# USB-DDC.net
KiCad netlist of a schematic drawn in EAGLE
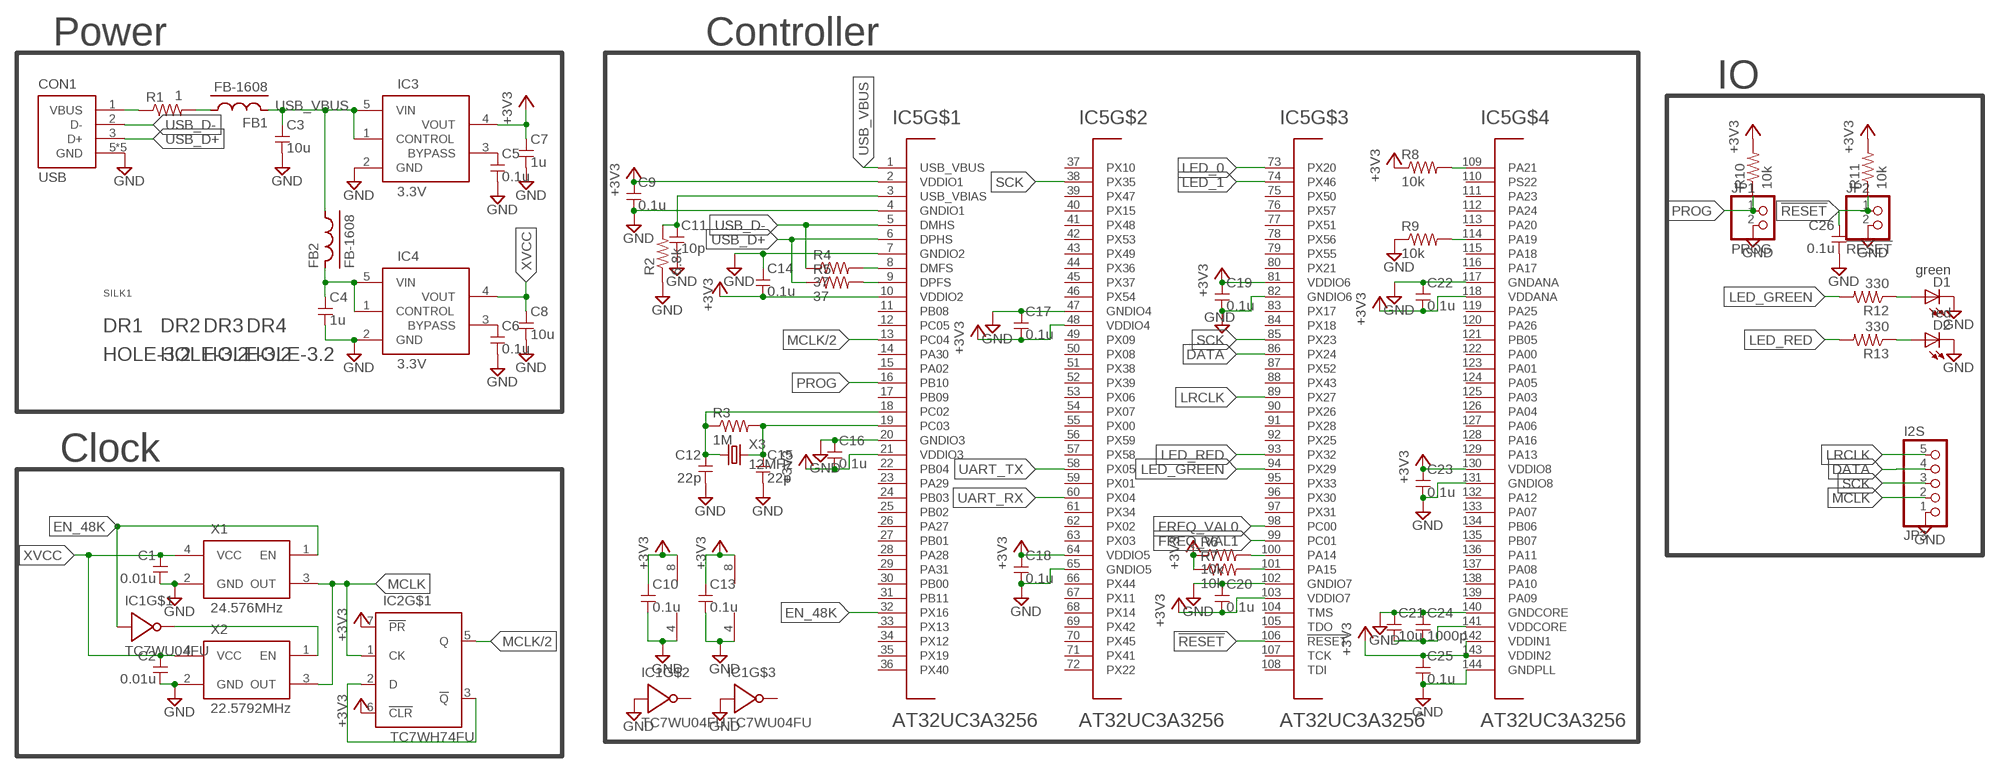
[diagram p0: schematic, sheet 1]

(export (version "E")
  (design (tool "Eeschema 10.0.6"))
  (components
    (comp (ref "C1")
      (value "0.01u")
      (footprint "eagle-import:1608")
      (libsource (lib "eagle-import") (part "C-1608"))
    )
    (comp (ref "C2")
      (value "0.01u")
      (footprint "eagle-import:1608")
      (libsource (lib "eagle-import") (part "C-1608"))
    )
    (comp (ref "C3")
      (value "10u")
      (footprint "eagle-import:2012")
      (libsource (lib "eagle-import") (part "C-2012"))
    )
    (comp (ref "C4")
      (value "1u")
      (footprint "eagle-import:1608")
      (libsource (lib "eagle-import") (part "C-1608"))
    )
    (comp (ref "C5")
      (value "0.1u")
      (footprint "eagle-import:1608")
      (libsource (lib "eagle-import") (part "C-1608"))
    )
    (comp (ref "C6")
      (value "0.1u")
      (footprint "eagle-import:1608")
      (libsource (lib "eagle-import") (part "C-1608"))
    )
    (comp (ref "C7")
      (value "1u")
      (footprint "eagle-import:2012")
      (libsource (lib "eagle-import") (part "C-2012"))
    )
    (comp (ref "C8")
      (value "10u")
      (footprint "eagle-import:2012")
      (libsource (lib "eagle-import") (part "C-2012"))
    )
    (comp (ref "C9")
      (value "0.1u")
      (footprint "eagle-import:1608")
      (libsource (lib "eagle-import") (part "C-1608"))
    )
    (comp (ref "C10")
      (value "0.1u")
      (footprint "eagle-import:1608")
      (libsource (lib "eagle-import") (part "C-1608"))
    )
    (comp (ref "C11")
      (value "10p")
      (footprint "eagle-import:1608")
      (libsource (lib "eagle-import") (part "C-1608"))
    )
    (comp (ref "C12")
      (value "22p")
      (footprint "eagle-import:1608")
      (libsource (lib "eagle-import") (part "C-1608"))
    )
    (comp (ref "C13")
      (value "0.1u")
      (footprint "eagle-import:1608")
      (libsource (lib "eagle-import") (part "C-1608"))
    )
    (comp (ref "C14")
      (value "0.1u")
      (footprint "eagle-import:1608")
      (libsource (lib "eagle-import") (part "C-1608"))
    )
    (comp (ref "C15")
      (value "22p")
      (footprint "eagle-import:1608")
      (libsource (lib "eagle-import") (part "C-1608"))
    )
    (comp (ref "C16")
      (value "0.1u")
      (footprint "eagle-import:1608")
      (libsource (lib "eagle-import") (part "C-1608"))
    )
    (comp (ref "C17")
      (value "0.1u")
      (footprint "eagle-import:1608")
      (libsource (lib "eagle-import") (part "C-1608"))
    )
    (comp (ref "C18")
      (value "0.1u")
      (footprint "eagle-import:1608")
      (libsource (lib "eagle-import") (part "C-1608"))
    )
    (comp (ref "C19")
      (value "0.1u")
      (footprint "eagle-import:1608")
      (libsource (lib "eagle-import") (part "C-1608"))
    )
    (comp (ref "C20")
      (value "0.1u")
      (footprint "eagle-import:1608")
      (libsource (lib "eagle-import") (part "C-1608"))
    )
    (comp (ref "C21")
      (value "10u")
      (footprint "eagle-import:2012")
      (libsource (lib "eagle-import") (part "C-2012"))
    )
    (comp (ref "C22")
      (value "0.1u")
      (footprint "eagle-import:1608")
      (libsource (lib "eagle-import") (part "C-1608"))
    )
    (comp (ref "C23")
      (value "0.1u")
      (footprint "eagle-import:1608")
      (libsource (lib "eagle-import") (part "C-1608"))
    )
    (comp (ref "C24")
      (value "1000p")
      (footprint "eagle-import:1608")
      (libsource (lib "eagle-import") (part "C-1608"))
    )
    (comp (ref "C25")
      (value "0.1u")
      (footprint "eagle-import:1608")
      (libsource (lib "eagle-import") (part "C-1608"))
    )
    (comp (ref "C26")
      (value "0.1u")
      (footprint "eagle-import:1608")
      (libsource (lib "eagle-import") (part "C-1608"))
    )
    (comp (ref "CON1")
      (value "USB")
      (footprint "eagle-import:UX60A-MB-5ST")
      (libsource (lib "eagle-import") (part "USB"))
    )
    (comp (ref "D1")
      (value "green")
      (footprint "eagle-import:D1608")
      (libsource (lib "eagle-import") (part "LED-SMD1608"))
    )
    (comp (ref "D2")
      (value "red")
      (footprint "eagle-import:D1608")
      (libsource (lib "eagle-import") (part "LED-SMD1608"))
    )
    (comp (ref "DR1")
      (value "HOLE-3.2")
      (footprint "eagle-import:HOLE_3.2")
      (libsource (lib "eagle-import") (part "HOLE-3.2"))
    )
    (comp (ref "DR2")
      (value "HOLE-3.2")
      (footprint "eagle-import:HOLE_3.2")
      (libsource (lib "eagle-import") (part "HOLE-3.2"))
    )
    (comp (ref "DR3")
      (value "HOLE-3.2")
      (footprint "eagle-import:HOLE_3.2")
      (libsource (lib "eagle-import") (part "HOLE-3.2"))
    )
    (comp (ref "DR4")
      (value "HOLE-3.2")
      (footprint "eagle-import:HOLE_3.2")
      (libsource (lib "eagle-import") (part "HOLE-3.2"))
    )
    (comp (ref "FB1")
      (value "FB-1608")
      (footprint "eagle-import:1608")
      (libsource (lib "eagle-import") (part "FB-1608"))
    )
    (comp (ref "FB2")
      (value "FB-1608")
      (footprint "eagle-import:1608")
      (libsource (lib "eagle-import") (part "FB-1608"))
    )
    (comp (ref "IC1")
      (value "TC7WU04FU")
      (footprint "eagle-import:SSOP8-P-0.65")
      (libsource (lib "eagle-import") (part "TC7WU04FU"))
    )
    (comp (ref "IC2")
      (value "TC7WH74FU")
      (footprint "eagle-import:SSOP8-P-0.65")
      (libsource (lib "eagle-import") (part "TC7WH74FU"))
    )
    (comp (ref "IC3")
      (value "3.3V")
      (footprint "eagle-import:SOT23-5")
      (libsource (lib "eagle-import") (part "NJM2863"))
    )
    (comp (ref "IC4")
      (value "3.3V")
      (footprint "eagle-import:SOT23-5")
      (libsource (lib "eagle-import") (part "NJM2863"))
    )
    (comp (ref "IC5")
      (value "AT32UC3A3256")
      (footprint "eagle-import:TQFP144")
      (libsource (lib "eagle-import") (part "AT32UC3A3256"))
    )
    (comp (ref "JP1")
      (value "PROG")
      (footprint "eagle-import:1X02")
      (libsource (lib "eagle-import") (part "PINHD-1X2"))
    )
    (comp (ref "JP2")
      (value "!RESET")
      (footprint "eagle-import:1X02")
      (libsource (lib "eagle-import") (part "PINHD-1X2"))
    )
    (comp (ref "JP3")
      (value "I2S")
      (footprint "eagle-import:1X05")
      (libsource (lib "eagle-import") (part "PINHD-1X5"))
    )
    (comp (ref "R1")
      (value "1")
      (footprint "eagle-import:0204_7")
      (libsource (lib "eagle-import") (part "R-7.5"))
    )
    (comp (ref "R2")
      (value "6.8k")
      (footprint "eagle-import:1608")
      (libsource (lib "eagle-import") (part "R-1608"))
    )
    (comp (ref "R3")
      (value "1M")
      (footprint "eagle-import:0204_7")
      (libsource (lib "eagle-import") (part "R-7.5"))
    )
    (comp (ref "R4")
      (value "37")
      (footprint "eagle-import:1608")
      (libsource (lib "eagle-import") (part "R-1608"))
    )
    (comp (ref "R5")
      (value "37")
      (footprint "eagle-import:1608")
      (libsource (lib "eagle-import") (part "R-1608"))
    )
    (comp (ref "R6")
      (value "10k")
      (footprint "eagle-import:1608")
      (libsource (lib "eagle-import") (part "R-1608"))
    )
    (comp (ref "R7")
      (value "10k")
      (footprint "eagle-import:1608")
      (libsource (lib "eagle-import") (part "R-1608"))
    )
    (comp (ref "R8")
      (value "10k")
      (footprint "eagle-import:1608")
      (libsource (lib "eagle-import") (part "R-1608"))
    )
    (comp (ref "R9")
      (value "10k")
      (footprint "eagle-import:1608")
      (libsource (lib "eagle-import") (part "R-1608"))
    )
    (comp (ref "R10")
      (value "10k")
      (footprint "eagle-import:1608")
      (libsource (lib "eagle-import") (part "R-1608"))
    )
    (comp (ref "R11")
      (value "10k")
      (footprint "eagle-import:1608")
      (libsource (lib "eagle-import") (part "R-1608"))
    )
    (comp (ref "R12")
      (value "330")
      (footprint "eagle-import:1608")
      (libsource (lib "eagle-import") (part "R-1608"))
    )
    (comp (ref "R13")
      (value "330")
      (footprint "eagle-import:1608")
      (libsource (lib "eagle-import") (part "R-1608"))
    )
    (comp (ref "SILK1")
      (value "ROBOTECHWHEELSILK-9MM")
      (footprint "eagle-import:ROBOTECHWHEEL-9MM")
      (libsource (lib "eagle-import") (part "ROBOTECHWHEELSILK-9MM"))
    )
    (comp (ref "X1")
      (value "24.576MHz")
      (footprint "eagle-import:KC7050")
      (libsource (lib "eagle-import") (part "OSC-KC7050"))
    )
    (comp (ref "X2")
      (value "22.5792MHz")
      (footprint "eagle-import:KC7050")
      (libsource (lib "eagle-import") (part "OSC-KC7050"))
    )
    (comp (ref "X3")
      (value "12MHz")
      (footprint "eagle-import:HC49_S")
      (libsource (lib "eagle-import") (part "CRYSTALHC49S"))
    )
  )
  (nets
    (net (code "1") (name "+3V3") (class "Default")
      (node (ref "C10") (pin "1") (pinfunction "1_1") (pintype "passive"))
      (node (ref "C13") (pin "1") (pinfunction "1_1") (pintype "passive"))
      (node (ref "C14") (pin "2") (pinfunction "2_2") (pintype "passive"))
      (node (ref "C16") (pin "2") (pinfunction "2_2") (pintype "passive"))
      (node (ref "C17") (pin "2") (pinfunction "2_2") (pintype "passive"))
      (node (ref "C18") (pin "1") (pinfunction "1_1") (pintype "passive"))
      (node (ref "C19") (pin "1") (pinfunction "1_1") (pintype "passive"))
      (node (ref "C20") (pin "2") (pinfunction "2_2") (pintype "passive"))
      (node (ref "C22") (pin "2") (pinfunction "2_2") (pintype "passive"))
      (node (ref "C23") (pin "1") (pinfunction "1_1") (pintype "passive"))
      (node (ref "C25") (pin "1") (pinfunction "1_1") (pintype "passive"))
      (node (ref "C7") (pin "1") (pinfunction "1_1") (pintype "passive"))
      (node (ref "C9") (pin "1") (pinfunction "1_1") (pintype "passive"))
      (node (ref "IC1") (pin "8") (pinfunction "V+_8") (pintype "power_in"))
      (node (ref "IC2") (pin "6") (pinfunction "~{CLR}_6") (pintype "input"))
      (node (ref "IC2") (pin "7") (pinfunction "~{PR}_7") (pintype "input"))
      (node (ref "IC2") (pin "8") (pinfunction "V+_8") (pintype "power_in"))
      (node (ref "IC3") (pin "4") (pinfunction "VOUT_4") (pintype "power_in"))
      (node (ref "IC5") (pin "10") (pinfunction "VDDIO2_10") (pintype "power_in"))
      (node (ref "IC5") (pin "103") (pinfunction "VDDIO7_103") (pintype "power_in"))
      (node (ref "IC5") (pin "118") (pinfunction "VDDANA_118") (pintype "power_in"))
      (node (ref "IC5") (pin "130") (pinfunction "VDDIO8_130") (pintype "power_in"))
      (node (ref "IC5") (pin "142") (pinfunction "VDDIN1_142") (pintype "power_in"))
      (node (ref "IC5") (pin "143") (pinfunction "VDDIN2_143") (pintype "power_in"))
      (node (ref "IC5") (pin "2") (pinfunction "VDDIO1_2") (pintype "power_in"))
      (node (ref "IC5") (pin "21") (pinfunction "VDDIO3_21") (pintype "power_in"))
      (node (ref "IC5") (pin "48") (pinfunction "VDDIO4_48") (pintype "power_in"))
      (node (ref "IC5") (pin "64") (pinfunction "VDDIO5_64") (pintype "power_in"))
      (node (ref "IC5") (pin "81") (pinfunction "VDDIO6_81") (pintype "power_in"))
      (node (ref "R10") (pin "2") (pinfunction "2_2") (pintype "passive"))
      (node (ref "R11") (pin "2") (pinfunction "2_2") (pintype "passive"))
      (node (ref "R6") (pin "1") (pinfunction "1_1") (pintype "passive"))
      (node (ref "R7") (pin "1") (pinfunction "1_1") (pintype "passive"))
      (node (ref "R8") (pin "1") (pinfunction "1_1") (pintype "passive"))
    )
    (net (code "2") (name "/~{RESET}") (class "Default")
      (node (ref "C26") (pin "1") (pinfunction "1_1") (pintype "passive"))
      (node (ref "IC5") (pin "106") (pinfunction "~{RESET}_106") (pintype "input"))
      (node (ref "JP2") (pin "1") (pinfunction "1_1") (pintype "passive"))
      (node (ref "R11") (pin "1") (pinfunction "1_1") (pintype "passive"))
    )
    (net (code "3") (name "DATA") (class "Default")
      (node (ref "IC5") (pin "86") (pinfunction "PX24_86") (pintype "bidirectional"))
      (node (ref "JP3") (pin "4") (pinfunction "4_4") (pintype "passive"))
    )
    (net (code "4") (name "EN_48K") (class "Default")
      (node (ref "IC1") (pin "1") (pinfunction "P$1_1") (pintype "input"))
      (node (ref "IC5") (pin "32") (pinfunction "PX16_32") (pintype "bidirectional"))
      (node (ref "X1") (pin "1") (pinfunction "EN_1") (pintype "input"))
    )
    (net (code "5") (name "FREQ_VAL0") (class "Default")
      (node (ref "IC5") (pin "98") (pinfunction "PC00_98") (pintype "bidirectional"))
    )
    (net (code "6") (name "FREQ_VAL1") (class "Default")
      (node (ref "IC5") (pin "99") (pinfunction "PC01_99") (pintype "bidirectional"))
    )
    (net (code "7") (name "GND") (class "Default")
      (node (ref "C1") (pin "2") (pinfunction "2_2") (pintype "passive"))
      (node (ref "C10") (pin "2") (pinfunction "2_2") (pintype "passive"))
      (node (ref "C11") (pin "2") (pinfunction "2_2") (pintype "passive"))
      (node (ref "C12") (pin "2") (pinfunction "2_2") (pintype "passive"))
      (node (ref "C13") (pin "2") (pinfunction "2_2") (pintype "passive"))
      (node (ref "C14") (pin "1") (pinfunction "1_1") (pintype "passive"))
      (node (ref "C15") (pin "2") (pinfunction "2_2") (pintype "passive"))
      (node (ref "C16") (pin "1") (pinfunction "1_1") (pintype "passive"))
      (node (ref "C17") (pin "1") (pinfunction "1_1") (pintype "passive"))
      (node (ref "C18") (pin "2") (pinfunction "2_2") (pintype "passive"))
      (node (ref "C19") (pin "2") (pinfunction "2_2") (pintype "passive"))
      (node (ref "C2") (pin "2") (pinfunction "2_2") (pintype "passive"))
      (node (ref "C20") (pin "1") (pinfunction "1_1") (pintype "passive"))
      (node (ref "C21") (pin "1") (pinfunction "1_1") (pintype "passive"))
      (node (ref "C22") (pin "1") (pinfunction "1_1") (pintype "passive"))
      (node (ref "C23") (pin "2") (pinfunction "2_2") (pintype "passive"))
      (node (ref "C24") (pin "1") (pinfunction "1_1") (pintype "passive"))
      (node (ref "C25") (pin "2") (pinfunction "2_2") (pintype "passive"))
      (node (ref "C26") (pin "2") (pinfunction "2_2") (pintype "passive"))
      (node (ref "C3") (pin "2") (pinfunction "2_2") (pintype "passive"))
      (node (ref "C4") (pin "2") (pinfunction "2_2") (pintype "passive"))
      (node (ref "C5") (pin "2") (pinfunction "2_2") (pintype "passive"))
      (node (ref "C6") (pin "2") (pinfunction "2_2") (pintype "passive"))
      (node (ref "C7") (pin "2") (pinfunction "2_2") (pintype "passive"))
      (node (ref "C8") (pin "2") (pinfunction "2_2") (pintype "passive"))
      (node (ref "C9") (pin "2") (pinfunction "2_2") (pintype "passive"))
      (node (ref "CON1") (pin "5") (pinfunction "GND_5") (pintype "bidirectional"))
      (node (ref "CON1") (pin "M1") (pinfunction "GND_M1") (pintype "bidirectional"))
      (node (ref "CON1") (pin "M2") (pinfunction "GND_M2") (pintype "bidirectional"))
      (node (ref "CON1") (pin "M3") (pinfunction "GND_M3") (pintype "bidirectional"))
      (node (ref "CON1") (pin "M4") (pinfunction "GND_M4") (pintype "bidirectional"))
      (node (ref "D1") (pin "K") (pinfunction "K_K") (pintype "passive"))
      (node (ref "D2") (pin "K") (pinfunction "K_K") (pintype "passive"))
      (node (ref "IC1") (pin "3") (pinfunction "P$1_3") (pintype "input"))
      (node (ref "IC1") (pin "4") (pinfunction "V-_4") (pintype "power_in"))
      (node (ref "IC1") (pin "6") (pinfunction "P$1_6") (pintype "input"))
      (node (ref "IC2") (pin "4") (pinfunction "V-_4") (pintype "power_in"))
      (node (ref "IC3") (pin "2") (pinfunction "GND_2") (pintype "power_in"))
      (node (ref "IC4") (pin "2") (pinfunction "GND_2") (pintype "power_in"))
      (node (ref "IC5") (pin "102") (pinfunction "GNDIO7_102") (pintype "power_in"))
      (node (ref "IC5") (pin "117") (pinfunction "GNDANA_117") (pintype "power_in"))
      (node (ref "IC5") (pin "131") (pinfunction "GNDIO8_131") (pintype "power_in"))
      (node (ref "IC5") (pin "140") (pinfunction "GNDCORE_140") (pintype "power_in"))
      (node (ref "IC5") (pin "144") (pinfunction "GNDPLL_144") (pintype "power_in"))
      (node (ref "IC5") (pin "20") (pinfunction "GNDIO3_20") (pintype "power_in"))
      (node (ref "IC5") (pin "4") (pinfunction "GNDIO1_4") (pintype "power_in"))
      (node (ref "IC5") (pin "47") (pinfunction "GNDIO4_47") (pintype "power_in"))
      (node (ref "IC5") (pin "65") (pinfunction "GNDIO5_65") (pintype "power_in"))
      (node (ref "IC5") (pin "7") (pinfunction "GNDIO2_7") (pintype "power_in"))
      (node (ref "IC5") (pin "82") (pinfunction "GNDIO6_82") (pintype "power_in"))
      (node (ref "JP1") (pin "2") (pinfunction "2_2") (pintype "passive"))
      (node (ref "JP2") (pin "2") (pinfunction "2_2") (pintype "passive"))
      (node (ref "JP3") (pin "1") (pinfunction "1_1") (pintype "passive"))
      (node (ref "R2") (pin "1") (pinfunction "1_1") (pintype "passive"))
      (node (ref "R9") (pin "1") (pinfunction "1_1") (pintype "passive"))
      (node (ref "X1") (pin "2") (pinfunction "GND_2") (pintype "power_in"))
      (node (ref "X2") (pin "2") (pinfunction "GND_2") (pintype "power_in"))
    )
    (net (code "8") (name "LED_0") (class "Default")
      (node (ref "IC5") (pin "73") (pinfunction "PX20_73") (pintype "bidirectional"))
    )
    (net (code "9") (name "LED_1") (class "Default")
      (node (ref "IC5") (pin "74") (pinfunction "PX46_74") (pintype "bidirectional"))
    )
    (net (code "10") (name "LED_GREEN") (class "Default")
      (node (ref "IC5") (pin "94") (pinfunction "PX29_94") (pintype "bidirectional"))
      (node (ref "R12") (pin "2") (pinfunction "2_2") (pintype "passive"))
    )
    (net (code "11") (name "LED_RED") (class "Default")
      (node (ref "IC5") (pin "93") (pinfunction "PX32_93") (pintype "bidirectional"))
      (node (ref "R13") (pin "2") (pinfunction "2_2") (pintype "passive"))
    )
    (net (code "12") (name "LRCLK") (class "Default")
      (node (ref "IC5") (pin "89") (pinfunction "PX27_89") (pintype "bidirectional"))
      (node (ref "JP3") (pin "5") (pinfunction "5_5") (pintype "passive"))
    )
    (net (code "13") (name "MCLK") (class "Default")
      (node (ref "IC2") (pin "1") (pinfunction "CK_1") (pintype "input"))
      (node (ref "JP3") (pin "2") (pinfunction "2_2") (pintype "passive"))
      (node (ref "X1") (pin "3") (pinfunction "OUT_3") (pintype "output"))
      (node (ref "X2") (pin "3") (pinfunction "OUT_3") (pintype "output"))
    )
    (net (code "14") (name "MCLK{slash}2") (class "Default")
      (node (ref "IC2") (pin "5") (pinfunction "Q_5") (pintype "output"))
      (node (ref "IC5") (pin "13") (pinfunction "PC04_13") (pintype "bidirectional"))
    )
    (net (code "15") (name "Net-(CON1-VBUS)") (class "Default")
      (node (ref "CON1") (pin "1") (pinfunction "VBUS_1") (pintype "bidirectional"))
      (node (ref "R1") (pin "1") (pinfunction "1_1") (pintype "passive"))
    )
    (net (code "16") (name "Net-(D1-PadA)") (class "Default")
      (node (ref "D1") (pin "A") (pinfunction "A_A") (pintype "passive"))
      (node (ref "R12") (pin "1") (pinfunction "1_1") (pintype "passive"))
    )
    (net (code "17") (name "Net-(D2-PadA)") (class "Default")
      (node (ref "D2") (pin "A") (pinfunction "A_A") (pintype "passive"))
      (node (ref "R13") (pin "1") (pinfunction "1_1") (pintype "passive"))
    )
    (net (code "18") (name "Net-(FB1-Pad1)") (class "Default")
      (node (ref "FB1") (pin "1") (pinfunction "1_1") (pintype "passive"))
      (node (ref "R1") (pin "2") (pinfunction "2_2") (pintype "passive"))
    )
    (net (code "19") (name "Net-(IC1A-P$2)") (class "Default")
      (node (ref "IC1") (pin "7") (pinfunction "P$2_7") (pintype "output"))
      (node (ref "X2") (pin "1") (pinfunction "EN_1") (pintype "input"))
    )
    (net (code "20") (name "Net-(IC2A-D)") (class "Default")
      (node (ref "IC2") (pin "2") (pinfunction "D_2") (pintype "input"))
      (node (ref "IC2") (pin "3") (pinfunction "~{Q}_3") (pintype "output"))
    )
    (net (code "21") (name "Net-(IC3-BYPASS)") (class "Default")
      (node (ref "C5") (pin "1") (pinfunction "1_1") (pintype "passive"))
      (node (ref "IC3") (pin "3") (pinfunction "BYPASS_3") (pintype "passive"))
    )
    (net (code "22") (name "Net-(IC4-BYPASS)") (class "Default")
      (node (ref "C6") (pin "1") (pinfunction "1_1") (pintype "passive"))
      (node (ref "IC4") (pin "3") (pinfunction "BYPASS_3") (pintype "passive"))
    )
    (net (code "23") (name "Net-(IC4-CONTROL)") (class "Default")
      (node (ref "C4") (pin "1") (pinfunction "1_1") (pintype "passive"))
      (node (ref "FB2") (pin "2") (pinfunction "2_2") (pintype "passive"))
      (node (ref "IC4") (pin "1") (pinfunction "CONTROL_1") (pintype "input"))
      (node (ref "IC4") (pin "5") (pinfunction "VIN_5") (pintype "power_in"))
    )
    (net (code "24") (name "Net-(IC5A-DMFS)") (class "Default")
      (node (ref "IC5") (pin "8") (pinfunction "DMFS_8") (pintype "bidirectional"))
      (node (ref "R4") (pin "2") (pinfunction "2_2") (pintype "passive"))
    )
    (net (code "25") (name "Net-(IC5A-DPFS)") (class "Default")
      (node (ref "IC5") (pin "9") (pinfunction "DPFS_9") (pintype "bidirectional"))
      (node (ref "R5") (pin "2") (pinfunction "2_2") (pintype "passive"))
    )
    (net (code "26") (name "Net-(IC5A-PC02)") (class "Default")
      (node (ref "C12") (pin "1") (pinfunction "1_1") (pintype "passive"))
      (node (ref "IC5") (pin "18") (pinfunction "PC02_18") (pintype "bidirectional"))
      (node (ref "R3") (pin "1") (pinfunction "1_1") (pintype "passive"))
      (node (ref "X3") (pin "1") (pinfunction "1_1") (pintype "passive"))
    )
    (net (code "27") (name "Net-(IC5A-PC03)") (class "Default")
      (node (ref "C15") (pin "1") (pinfunction "1_1") (pintype "passive"))
      (node (ref "IC5") (pin "19") (pinfunction "PC03_19") (pintype "bidirectional"))
      (node (ref "R3") (pin "2") (pinfunction "2_2") (pintype "passive"))
      (node (ref "X3") (pin "2") (pinfunction "2_2") (pintype "passive"))
    )
    (net (code "28") (name "Net-(IC5A-USB_VBIAS)") (class "Default")
      (node (ref "C11") (pin "1") (pinfunction "1_1") (pintype "passive"))
      (node (ref "IC5") (pin "3") (pinfunction "USB_VBIAS_3") (pintype "input"))
      (node (ref "R2") (pin "2") (pinfunction "2_2") (pintype "passive"))
    )
    (net (code "29") (name "Net-(IC5C-PA14)") (class "Default")
      (node (ref "IC5") (pin "100") (pinfunction "PA14_100") (pintype "bidirectional"))
      (node (ref "R6") (pin "2") (pinfunction "2_2") (pintype "passive"))
    )
    (net (code "30") (name "Net-(IC5C-PA15)") (class "Default")
      (node (ref "IC5") (pin "101") (pinfunction "PA15_101") (pintype "bidirectional"))
      (node (ref "R7") (pin "2") (pinfunction "2_2") (pintype "passive"))
    )
    (net (code "31") (name "Net-(IC5D-PA19)") (class "Default")
      (node (ref "IC5") (pin "114") (pinfunction "PA19_114") (pintype "bidirectional"))
      (node (ref "R9") (pin "2") (pinfunction "2_2") (pintype "passive"))
    )
    (net (code "32") (name "Net-(IC5D-PA21)") (class "Default")
      (node (ref "IC5") (pin "109") (pinfunction "PA21_109") (pintype "bidirectional"))
      (node (ref "R8") (pin "2") (pinfunction "2_2") (pintype "passive"))
    )
    (net (code "33") (name "Net-(IC5D-VDDCORE)") (class "Default")
      (node (ref "C21") (pin "2") (pinfunction "2_2") (pintype "passive"))
      (node (ref "C24") (pin "2") (pinfunction "2_2") (pintype "passive"))
      (node (ref "IC5") (pin "141") (pinfunction "VDDCORE_141") (pintype "power_in"))
    )
    (net (code "34") (name "PROG") (class "Default")
      (node (ref "IC5") (pin "16") (pinfunction "PB10_16") (pintype "bidirectional"))
      (node (ref "JP1") (pin "1") (pinfunction "1_1") (pintype "passive"))
      (node (ref "R10") (pin "1") (pinfunction "1_1") (pintype "passive"))
    )
    (net (code "35") (name "SCK") (class "Default")
      (node (ref "IC5") (pin "38") (pinfunction "PX35_38") (pintype "bidirectional"))
      (node (ref "IC5") (pin "85") (pinfunction "PX23_85") (pintype "bidirectional"))
      (node (ref "JP3") (pin "3") (pinfunction "3_3") (pintype "passive"))
    )
    (net (code "36") (name "UART_RX") (class "Default")
      (node (ref "IC5") (pin "60") (pinfunction "PX04_60") (pintype "bidirectional"))
    )
    (net (code "37") (name "UART_TX") (class "Default")
      (node (ref "IC5") (pin "58") (pinfunction "PX05_58") (pintype "bidirectional"))
    )
    (net (code "38") (name "USB_D+") (class "Default")
      (node (ref "CON1") (pin "3") (pinfunction "D+_3") (pintype "bidirectional"))
      (node (ref "IC5") (pin "6") (pinfunction "DPHS_6") (pintype "bidirectional"))
      (node (ref "R5") (pin "1") (pinfunction "1_1") (pintype "passive"))
    )
    (net (code "39") (name "USB_D-") (class "Default")
      (node (ref "CON1") (pin "2") (pinfunction "D-_2") (pintype "bidirectional"))
      (node (ref "IC5") (pin "5") (pinfunction "DMHS_5") (pintype "bidirectional"))
      (node (ref "R4") (pin "1") (pinfunction "1_1") (pintype "passive"))
    )
    (net (code "40") (name "USB_VBUS") (class "Default")
      (node (ref "C3") (pin "1") (pinfunction "1_1") (pintype "passive"))
      (node (ref "FB1") (pin "2") (pinfunction "2_2") (pintype "passive"))
      (node (ref "FB2") (pin "1") (pinfunction "1_1") (pintype "passive"))
      (node (ref "IC3") (pin "1") (pinfunction "CONTROL_1") (pintype "input"))
      (node (ref "IC3") (pin "5") (pinfunction "VIN_5") (pintype "power_in"))
      (node (ref "IC5") (pin "1") (pinfunction "USB_VBUS_1") (pintype "input"))
    )
    (net (code "41") (name "XVCC") (class "Default")
      (node (ref "C1") (pin "1") (pinfunction "1_1") (pintype "passive"))
      (node (ref "C2") (pin "1") (pinfunction "1_1") (pintype "passive"))
      (node (ref "C8") (pin "1") (pinfunction "1_1") (pintype "passive"))
      (node (ref "IC4") (pin "4") (pinfunction "VOUT_4") (pintype "power_in"))
      (node (ref "X1") (pin "4") (pinfunction "VCC_4") (pintype "power_in"))
      (node (ref "X2") (pin "4") (pinfunction "VCC_4") (pintype "power_in"))
    )
    (net (code "42") (name "unconnected-(IC1B-P$2-Pad2)") (class "Default")
      (node (ref "IC1") (pin "2") (pinfunction "P$2_2") (pintype "output"))
    )
    (net (code "43") (name "unconnected-(IC1C-P$2-Pad5)") (class "Default")
      (node (ref "IC1") (pin "5") (pinfunction "P$2_5") (pintype "output"))
    )
    (net (code "44") (name "unconnected-(IC5A-PA02-Pad15)") (class "Default")
      (node (ref "IC5") (pin "15") (pinfunction "PA02_15") (pintype "bidirectional"))
    )
    (net (code "45") (name "unconnected-(IC5A-PA27-Pad26)") (class "Default")
      (node (ref "IC5") (pin "26") (pinfunction "PA27_26") (pintype "bidirectional"))
    )
    (net (code "46") (name "unconnected-(IC5A-PA28-Pad28)") (class "Default")
      (node (ref "IC5") (pin "28") (pinfunction "PA28_28") (pintype "bidirectional"))
    )
    (net (code "47") (name "unconnected-(IC5A-PA29-Pad23)") (class "Default")
      (node (ref "IC5") (pin "23") (pinfunction "PA29_23") (pintype "bidirectional"))
    )
    (net (code "48") (name "unconnected-(IC5A-PA30-Pad14)") (class "Default")
      (node (ref "IC5") (pin "14") (pinfunction "PA30_14") (pintype "bidirectional"))
    )
    (net (code "49") (name "unconnected-(IC5A-PA31-Pad29)") (class "Default")
      (node (ref "IC5") (pin "29") (pinfunction "PA31_29") (pintype "bidirectional"))
    )
    (net (code "50") (name "unconnected-(IC5A-PB00-Pad30)") (class "Default")
      (node (ref "IC5") (pin "30") (pinfunction "PB00_30") (pintype "bidirectional"))
    )
    (net (code "51") (name "unconnected-(IC5A-PB01-Pad27)") (class "Default")
      (node (ref "IC5") (pin "27") (pinfunction "PB01_27") (pintype "bidirectional"))
    )
    (net (code "52") (name "unconnected-(IC5A-PB02-Pad25)") (class "Default")
      (node (ref "IC5") (pin "25") (pinfunction "PB02_25") (pintype "bidirectional"))
    )
    (net (code "53") (name "unconnected-(IC5A-PB03-Pad24)") (class "Default")
      (node (ref "IC5") (pin "24") (pinfunction "PB03_24") (pintype "bidirectional"))
    )
    (net (code "54") (name "unconnected-(IC5A-PB04-Pad22)") (class "Default")
      (node (ref "IC5") (pin "22") (pinfunction "PB04_22") (pintype "bidirectional"))
    )
    (net (code "55") (name "unconnected-(IC5A-PB08-Pad11)") (class "Default")
      (node (ref "IC5") (pin "11") (pinfunction "PB08_11") (pintype "bidirectional"))
    )
    (net (code "56") (name "unconnected-(IC5A-PB09-Pad17)") (class "Default")
      (node (ref "IC5") (pin "17") (pinfunction "PB09_17") (pintype "bidirectional"))
    )
    (net (code "57") (name "unconnected-(IC5A-PB11-Pad31)") (class "Default")
      (node (ref "IC5") (pin "31") (pinfunction "PB11_31") (pintype "bidirectional"))
    )
    (net (code "58") (name "unconnected-(IC5A-PC05-Pad12)") (class "Default")
      (node (ref "IC5") (pin "12") (pinfunction "PC05_12") (pintype "bidirectional"))
    )
    (net (code "59") (name "unconnected-(IC5A-PX12-Pad34)") (class "Default")
      (node (ref "IC5") (pin "34") (pinfunction "PX12_34") (pintype "bidirectional"))
    )
    (net (code "60") (name "unconnected-(IC5A-PX13-Pad33)") (class "Default")
      (node (ref "IC5") (pin "33") (pinfunction "PX13_33") (pintype "bidirectional"))
    )
    (net (code "61") (name "unconnected-(IC5A-PX19-Pad35)") (class "Default")
      (node (ref "IC5") (pin "35") (pinfunction "PX19_35") (pintype "bidirectional"))
    )
    (net (code "62") (name "unconnected-(IC5A-PX40-Pad36)") (class "Default")
      (node (ref "IC5") (pin "36") (pinfunction "PX40_36") (pintype "bidirectional"))
    )
    (net (code "63") (name "unconnected-(IC5B-PX00-Pad55)") (class "Default")
      (node (ref "IC5") (pin "55") (pinfunction "PX00_55") (pintype "bidirectional"))
    )
    (net (code "64") (name "unconnected-(IC5B-PX01-Pad59)") (class "Default")
      (node (ref "IC5") (pin "59") (pinfunction "PX01_59") (pintype "bidirectional"))
    )
    (net (code "65") (name "unconnected-(IC5B-PX02-Pad62)") (class "Default")
      (node (ref "IC5") (pin "62") (pinfunction "PX02_62") (pintype "bidirectional"))
    )
    (net (code "66") (name "unconnected-(IC5B-PX03-Pad63)") (class "Default")
      (node (ref "IC5") (pin "63") (pinfunction "PX03_63") (pintype "bidirectional"))
    )
    (net (code "67") (name "unconnected-(IC5B-PX06-Pad53)") (class "Default")
      (node (ref "IC5") (pin "53") (pinfunction "PX06_53") (pintype "bidirectional"))
    )
    (net (code "68") (name "unconnected-(IC5B-PX07-Pad54)") (class "Default")
      (node (ref "IC5") (pin "54") (pinfunction "PX07_54") (pintype "bidirectional"))
    )
    (net (code "69") (name "unconnected-(IC5B-PX08-Pad50)") (class "Default")
      (node (ref "IC5") (pin "50") (pinfunction "PX08_50") (pintype "bidirectional"))
    )
    (net (code "70") (name "unconnected-(IC5B-PX09-Pad49)") (class "Default")
      (node (ref "IC5") (pin "49") (pinfunction "PX09_49") (pintype "bidirectional"))
    )
    (net (code "71") (name "unconnected-(IC5B-PX10-Pad37)") (class "Default")
      (node (ref "IC5") (pin "37") (pinfunction "PX10_37") (pintype "bidirectional"))
    )
    (net (code "72") (name "unconnected-(IC5B-PX11-Pad67)") (class "Default")
      (node (ref "IC5") (pin "67") (pinfunction "PX11_67") (pintype "bidirectional"))
    )
    (net (code "73") (name "unconnected-(IC5B-PX14-Pad68)") (class "Default")
      (node (ref "IC5") (pin "68") (pinfunction "PX14_68") (pintype "bidirectional"))
    )
    (net (code "74") (name "unconnected-(IC5B-PX15-Pad40)") (class "Default")
      (node (ref "IC5") (pin "40") (pinfunction "PX15_40") (pintype "bidirectional"))
    )
    (net (code "75") (name "unconnected-(IC5B-PX22-Pad72)") (class "Default")
      (node (ref "IC5") (pin "72") (pinfunction "PX22_72") (pintype "bidirectional"))
    )
    (net (code "76") (name "unconnected-(IC5B-PX34-Pad61)") (class "Default")
      (node (ref "IC5") (pin "61") (pinfunction "PX34_61") (pintype "bidirectional"))
    )
    (net (code "77") (name "unconnected-(IC5B-PX36-Pad44)") (class "Default")
      (node (ref "IC5") (pin "44") (pinfunction "PX36_44") (pintype "bidirectional"))
    )
    (net (code "78") (name "unconnected-(IC5B-PX37-Pad45)") (class "Default")
      (node (ref "IC5") (pin "45") (pinfunction "PX37_45") (pintype "bidirectional"))
    )
    (net (code "79") (name "unconnected-(IC5B-PX38-Pad51)") (class "Default")
      (node (ref "IC5") (pin "51") (pinfunction "PX38_51") (pintype "bidirectional"))
    )
    (net (code "80") (name "unconnected-(IC5B-PX39-Pad52)") (class "Default")
      (node (ref "IC5") (pin "52") (pinfunction "PX39_52") (pintype "bidirectional"))
    )
    (net (code "81") (name "unconnected-(IC5B-PX41-Pad71)") (class "Default")
      (node (ref "IC5") (pin "71") (pinfunction "PX41_71") (pintype "bidirectional"))
    )
    (net (code "82") (name "unconnected-(IC5B-PX42-Pad69)") (class "Default")
      (node (ref "IC5") (pin "69") (pinfunction "PX42_69") (pintype "bidirectional"))
    )
    (net (code "83") (name "unconnected-(IC5B-PX44-Pad66)") (class "Default")
      (node (ref "IC5") (pin "66") (pinfunction "PX44_66") (pintype "bidirectional"))
    )
    (net (code "84") (name "unconnected-(IC5B-PX45-Pad70)") (class "Default")
      (node (ref "IC5") (pin "70") (pinfunction "PX45_70") (pintype "bidirectional"))
    )
    (net (code "85") (name "unconnected-(IC5B-PX47-Pad39)") (class "Default")
      (node (ref "IC5") (pin "39") (pinfunction "PX47_39") (pintype "bidirectional"))
    )
    (net (code "86") (name "unconnected-(IC5B-PX48-Pad41)") (class "Default")
      (node (ref "IC5") (pin "41") (pinfunction "PX48_41") (pintype "bidirectional"))
    )
    (net (code "87") (name "unconnected-(IC5B-PX49-Pad43)") (class "Default")
      (node (ref "IC5") (pin "43") (pinfunction "PX49_43") (pintype "bidirectional"))
    )
    (net (code "88") (name "unconnected-(IC5B-PX53-Pad42)") (class "Default")
      (node (ref "IC5") (pin "42") (pinfunction "PX53_42") (pintype "bidirectional"))
    )
    (net (code "89") (name "unconnected-(IC5B-PX54-Pad46)") (class "Default")
      (node (ref "IC5") (pin "46") (pinfunction "PX54_46") (pintype "bidirectional"))
    )
    (net (code "90") (name "unconnected-(IC5B-PX58-Pad57)") (class "Default")
      (node (ref "IC5") (pin "57") (pinfunction "PX58_57") (pintype "bidirectional"))
    )
    (net (code "91") (name "unconnected-(IC5B-PX59-Pad56)") (class "Default")
      (node (ref "IC5") (pin "56") (pinfunction "PX59_56") (pintype "bidirectional"))
    )
    (net (code "92") (name "unconnected-(IC5C-PX17-Pad83)") (class "Default")
      (node (ref "IC5") (pin "83") (pinfunction "PX17_83") (pintype "bidirectional"))
    )
    (net (code "93") (name "unconnected-(IC5C-PX18-Pad84)") (class "Default")
      (node (ref "IC5") (pin "84") (pinfunction "PX18_84") (pintype "bidirectional"))
    )
    (net (code "94") (name "unconnected-(IC5C-PX21-Pad80)") (class "Default")
      (node (ref "IC5") (pin "80") (pinfunction "PX21_80") (pintype "bidirectional"))
    )
    (net (code "95") (name "unconnected-(IC5C-PX25-Pad92)") (class "Default")
      (node (ref "IC5") (pin "92") (pinfunction "PX25_92") (pintype "bidirectional"))
    )
    (net (code "96") (name "unconnected-(IC5C-PX26-Pad90)") (class "Default")
      (node (ref "IC5") (pin "90") (pinfunction "PX26_90") (pintype "bidirectional"))
    )
    (net (code "97") (name "unconnected-(IC5C-PX28-Pad91)") (class "Default")
      (node (ref "IC5") (pin "91") (pinfunction "PX28_91") (pintype "bidirectional"))
    )
    (net (code "98") (name "unconnected-(IC5C-PX30-Pad96)") (class "Default")
      (node (ref "IC5") (pin "96") (pinfunction "PX30_96") (pintype "bidirectional"))
    )
    (net (code "99") (name "unconnected-(IC5C-PX31-Pad97)") (class "Default")
      (node (ref "IC5") (pin "97") (pinfunction "PX31_97") (pintype "bidirectional"))
    )
    (net (code "100") (name "unconnected-(IC5C-PX33-Pad95)") (class "Default")
      (node (ref "IC5") (pin "95") (pinfunction "PX33_95") (pintype "bidirectional"))
    )
    (net (code "101") (name "unconnected-(IC5C-PX43-Pad88)") (class "Default")
      (node (ref "IC5") (pin "88") (pinfunction "PX43_88") (pintype "bidirectional"))
    )
    (net (code "102") (name "unconnected-(IC5C-PX50-Pad75)") (class "Default")
      (node (ref "IC5") (pin "75") (pinfunction "PX50_75") (pintype "bidirectional"))
    )
    (net (code "103") (name "unconnected-(IC5C-PX51-Pad77)") (class "Default")
      (node (ref "IC5") (pin "77") (pinfunction "PX51_77") (pintype "bidirectional"))
    )
    (net (code "104") (name "unconnected-(IC5C-PX52-Pad87)") (class "Default")
      (node (ref "IC5") (pin "87") (pinfunction "PX52_87") (pintype "bidirectional"))
    )
    (net (code "105") (name "unconnected-(IC5C-PX55-Pad79)") (class "Default")
      (node (ref "IC5") (pin "79") (pinfunction "PX55_79") (pintype "bidirectional"))
    )
    (net (code "106") (name "unconnected-(IC5C-PX56-Pad78)") (class "Default")
      (node (ref "IC5") (pin "78") (pinfunction "PX56_78") (pintype "bidirectional"))
    )
    (net (code "107") (name "unconnected-(IC5C-PX57-Pad76)") (class "Default")
      (node (ref "IC5") (pin "76") (pinfunction "PX57_76") (pintype "bidirectional"))
    )
    (net (code "108") (name "unconnected-(IC5C-TCK-Pad107)") (class "Default")
      (node (ref "IC5") (pin "107") (pinfunction "TCK_107") (pintype "bidirectional"))
    )
    (net (code "109") (name "unconnected-(IC5C-TDI-Pad108)") (class "Default")
      (node (ref "IC5") (pin "108") (pinfunction "TDI_108") (pintype "bidirectional"))
    )
    (net (code "110") (name "unconnected-(IC5C-TDO-Pad105)") (class "Default")
      (node (ref "IC5") (pin "105") (pinfunction "TDO_105") (pintype "bidirectional"))
    )
    (net (code "111") (name "unconnected-(IC5C-TMS-Pad104)") (class "Default")
      (node (ref "IC5") (pin "104") (pinfunction "TMS_104") (pintype "bidirectional"))
    )
    (net (code "112") (name "unconnected-(IC5D-PA00-Pad122)") (class "Default")
      (node (ref "IC5") (pin "122") (pinfunction "PA00_122") (pintype "bidirectional"))
    )
    (net (code "113") (name "unconnected-(IC5D-PA01-Pad123)") (class "Default")
      (node (ref "IC5") (pin "123") (pinfunction "PA01_123") (pintype "bidirectional"))
    )
    (net (code "114") (name "unconnected-(IC5D-PA03-Pad125)") (class "Default")
      (node (ref "IC5") (pin "125") (pinfunction "PA03_125") (pintype "bidirectional"))
    )
    (net (code "115") (name "unconnected-(IC5D-PA04-Pad126)") (class "Default")
      (node (ref "IC5") (pin "126") (pinfunction "PA04_126") (pintype "bidirectional"))
    )
    (net (code "116") (name "unconnected-(IC5D-PA05-Pad124)") (class "Default")
      (node (ref "IC5") (pin "124") (pinfunction "PA05_124") (pintype "bidirectional"))
    )
    (net (code "117") (name "unconnected-(IC5D-PA06-Pad127)") (class "Default")
      (node (ref "IC5") (pin "127") (pinfunction "PA06_127") (pintype "bidirectional"))
    )
    (net (code "118") (name "unconnected-(IC5D-PA07-Pad133)") (class "Default")
      (node (ref "IC5") (pin "133") (pinfunction "PA07_133") (pintype "bidirectional"))
    )
    (net (code "119") (name "unconnected-(IC5D-PA08-Pad137)") (class "Default")
      (node (ref "IC5") (pin "137") (pinfunction "PA08_137") (pintype "bidirectional"))
    )
    (net (code "120") (name "unconnected-(IC5D-PA09-Pad139)") (class "Default")
      (node (ref "IC5") (pin "139") (pinfunction "PA09_139") (pintype "bidirectional"))
    )
    (net (code "121") (name "unconnected-(IC5D-PA10-Pad138)") (class "Default")
      (node (ref "IC5") (pin "138") (pinfunction "PA10_138") (pintype "bidirectional"))
    )
    (net (code "122") (name "unconnected-(IC5D-PA11-Pad136)") (class "Default")
      (node (ref "IC5") (pin "136") (pinfunction "PA11_136") (pintype "bidirectional"))
    )
    (net (code "123") (name "unconnected-(IC5D-PA12-Pad132)") (class "Default")
      (node (ref "IC5") (pin "132") (pinfunction "PA12_132") (pintype "bidirectional"))
    )
    (net (code "124") (name "unconnected-(IC5D-PA13-Pad129)") (class "Default")
      (node (ref "IC5") (pin "129") (pinfunction "PA13_129") (pintype "bidirectional"))
    )
    (net (code "125") (name "unconnected-(IC5D-PA16-Pad128)") (class "Default")
      (node (ref "IC5") (pin "128") (pinfunction "PA16_128") (pintype "bidirectional"))
    )
    (net (code "126") (name "unconnected-(IC5D-PA17-Pad116)") (class "Default")
      (node (ref "IC5") (pin "116") (pinfunction "PA17_116") (pintype "bidirectional"))
    )
    (net (code "127") (name "unconnected-(IC5D-PA18-Pad115)") (class "Default")
      (node (ref "IC5") (pin "115") (pinfunction "PA18_115") (pintype "bidirectional"))
    )
    (net (code "128") (name "unconnected-(IC5D-PA20-Pad113)") (class "Default")
      (node (ref "IC5") (pin "113") (pinfunction "PA20_113") (pintype "bidirectional"))
    )
    (net (code "129") (name "unconnected-(IC5D-PA23-Pad111)") (class "Default")
      (node (ref "IC5") (pin "111") (pinfunction "PA23_111") (pintype "bidirectional"))
    )
    (net (code "130") (name "unconnected-(IC5D-PA24-Pad112)") (class "Default")
      (node (ref "IC5") (pin "112") (pinfunction "PA24_112") (pintype "bidirectional"))
    )
    (net (code "131") (name "unconnected-(IC5D-PA25-Pad119)") (class "Default")
      (node (ref "IC5") (pin "119") (pinfunction "PA25_119") (pintype "bidirectional"))
    )
    (net (code "132") (name "unconnected-(IC5D-PA26-Pad120)") (class "Default")
      (node (ref "IC5") (pin "120") (pinfunction "PA26_120") (pintype "bidirectional"))
    )
    (net (code "133") (name "unconnected-(IC5D-PB05-Pad121)") (class "Default")
      (node (ref "IC5") (pin "121") (pinfunction "PB05_121") (pintype "bidirectional"))
    )
    (net (code "134") (name "unconnected-(IC5D-PB06-Pad134)") (class "Default")
      (node (ref "IC5") (pin "134") (pinfunction "PB06_134") (pintype "bidirectional"))
    )
    (net (code "135") (name "unconnected-(IC5D-PB07-Pad135)") (class "Default")
      (node (ref "IC5") (pin "135") (pinfunction "PB07_135") (pintype "bidirectional"))
    )
    (net (code "136") (name "unconnected-(IC5D-PS22-Pad110)") (class "Default")
      (node (ref "IC5") (pin "110") (pinfunction "PS22_110") (pintype "bidirectional"))
    )
  )
)
